# berthaBluetooth.net
KiCad netlist of a schematic drawn in EAGLE
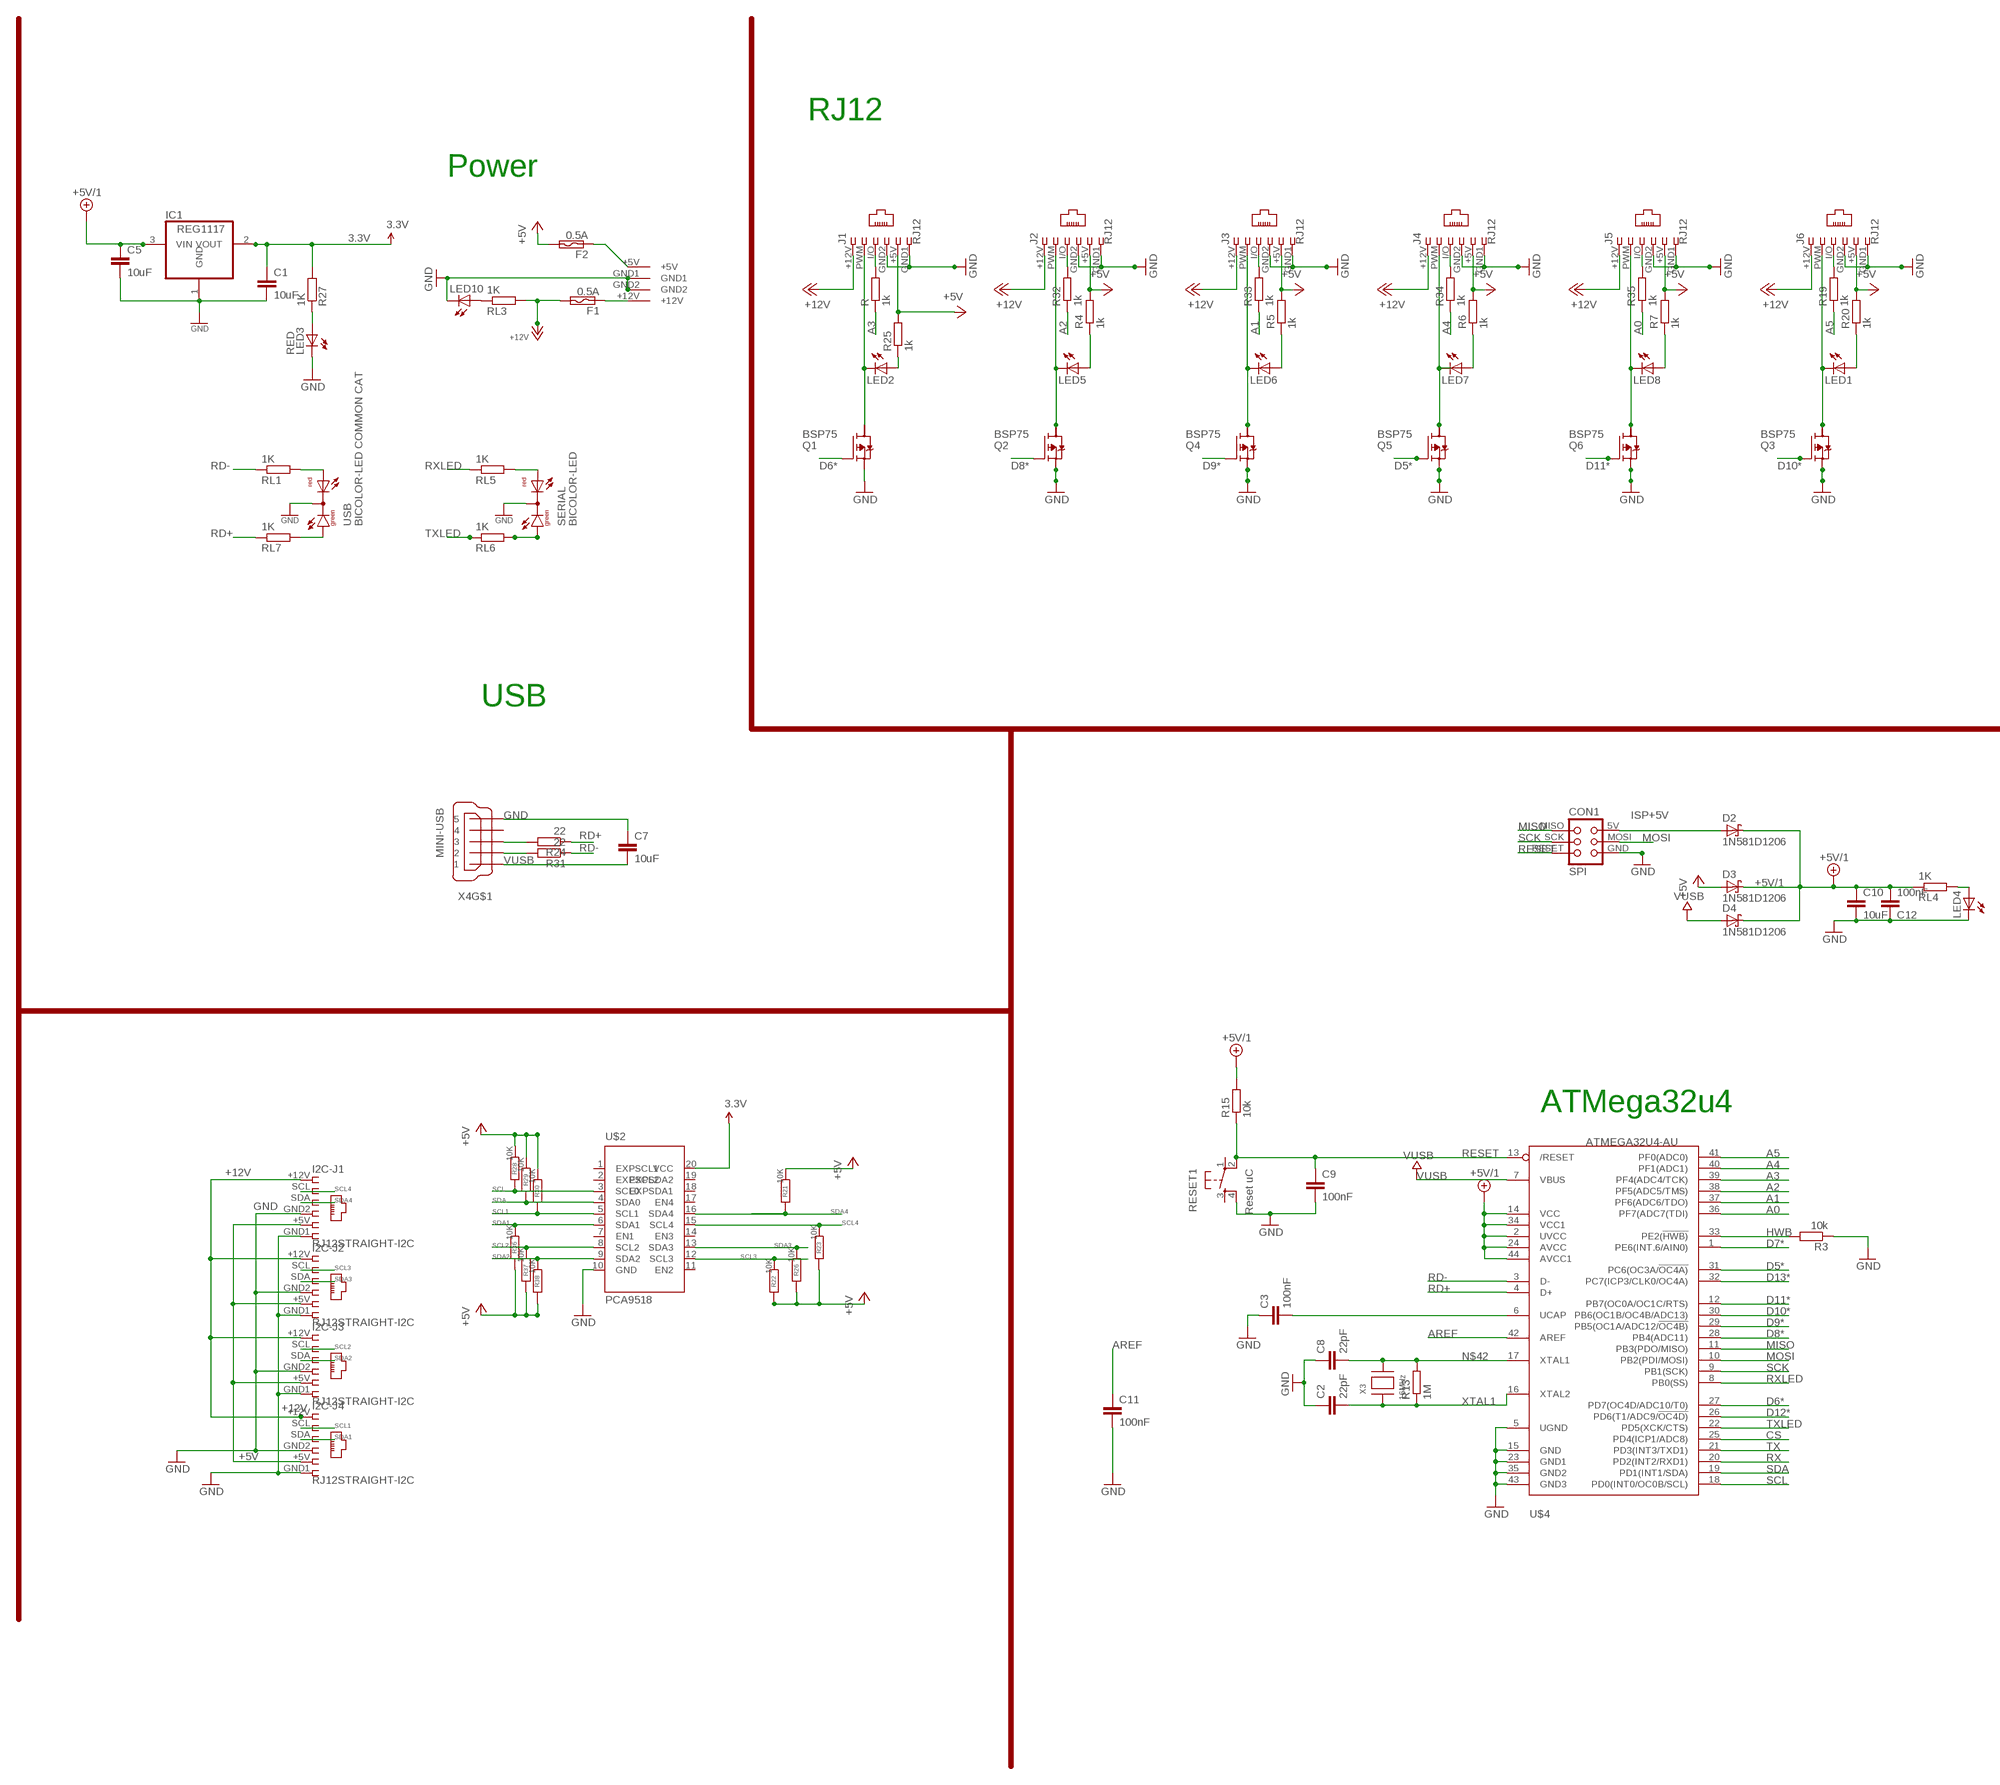
[diagram p0: schematic, sheet 1, part 1 of 2]
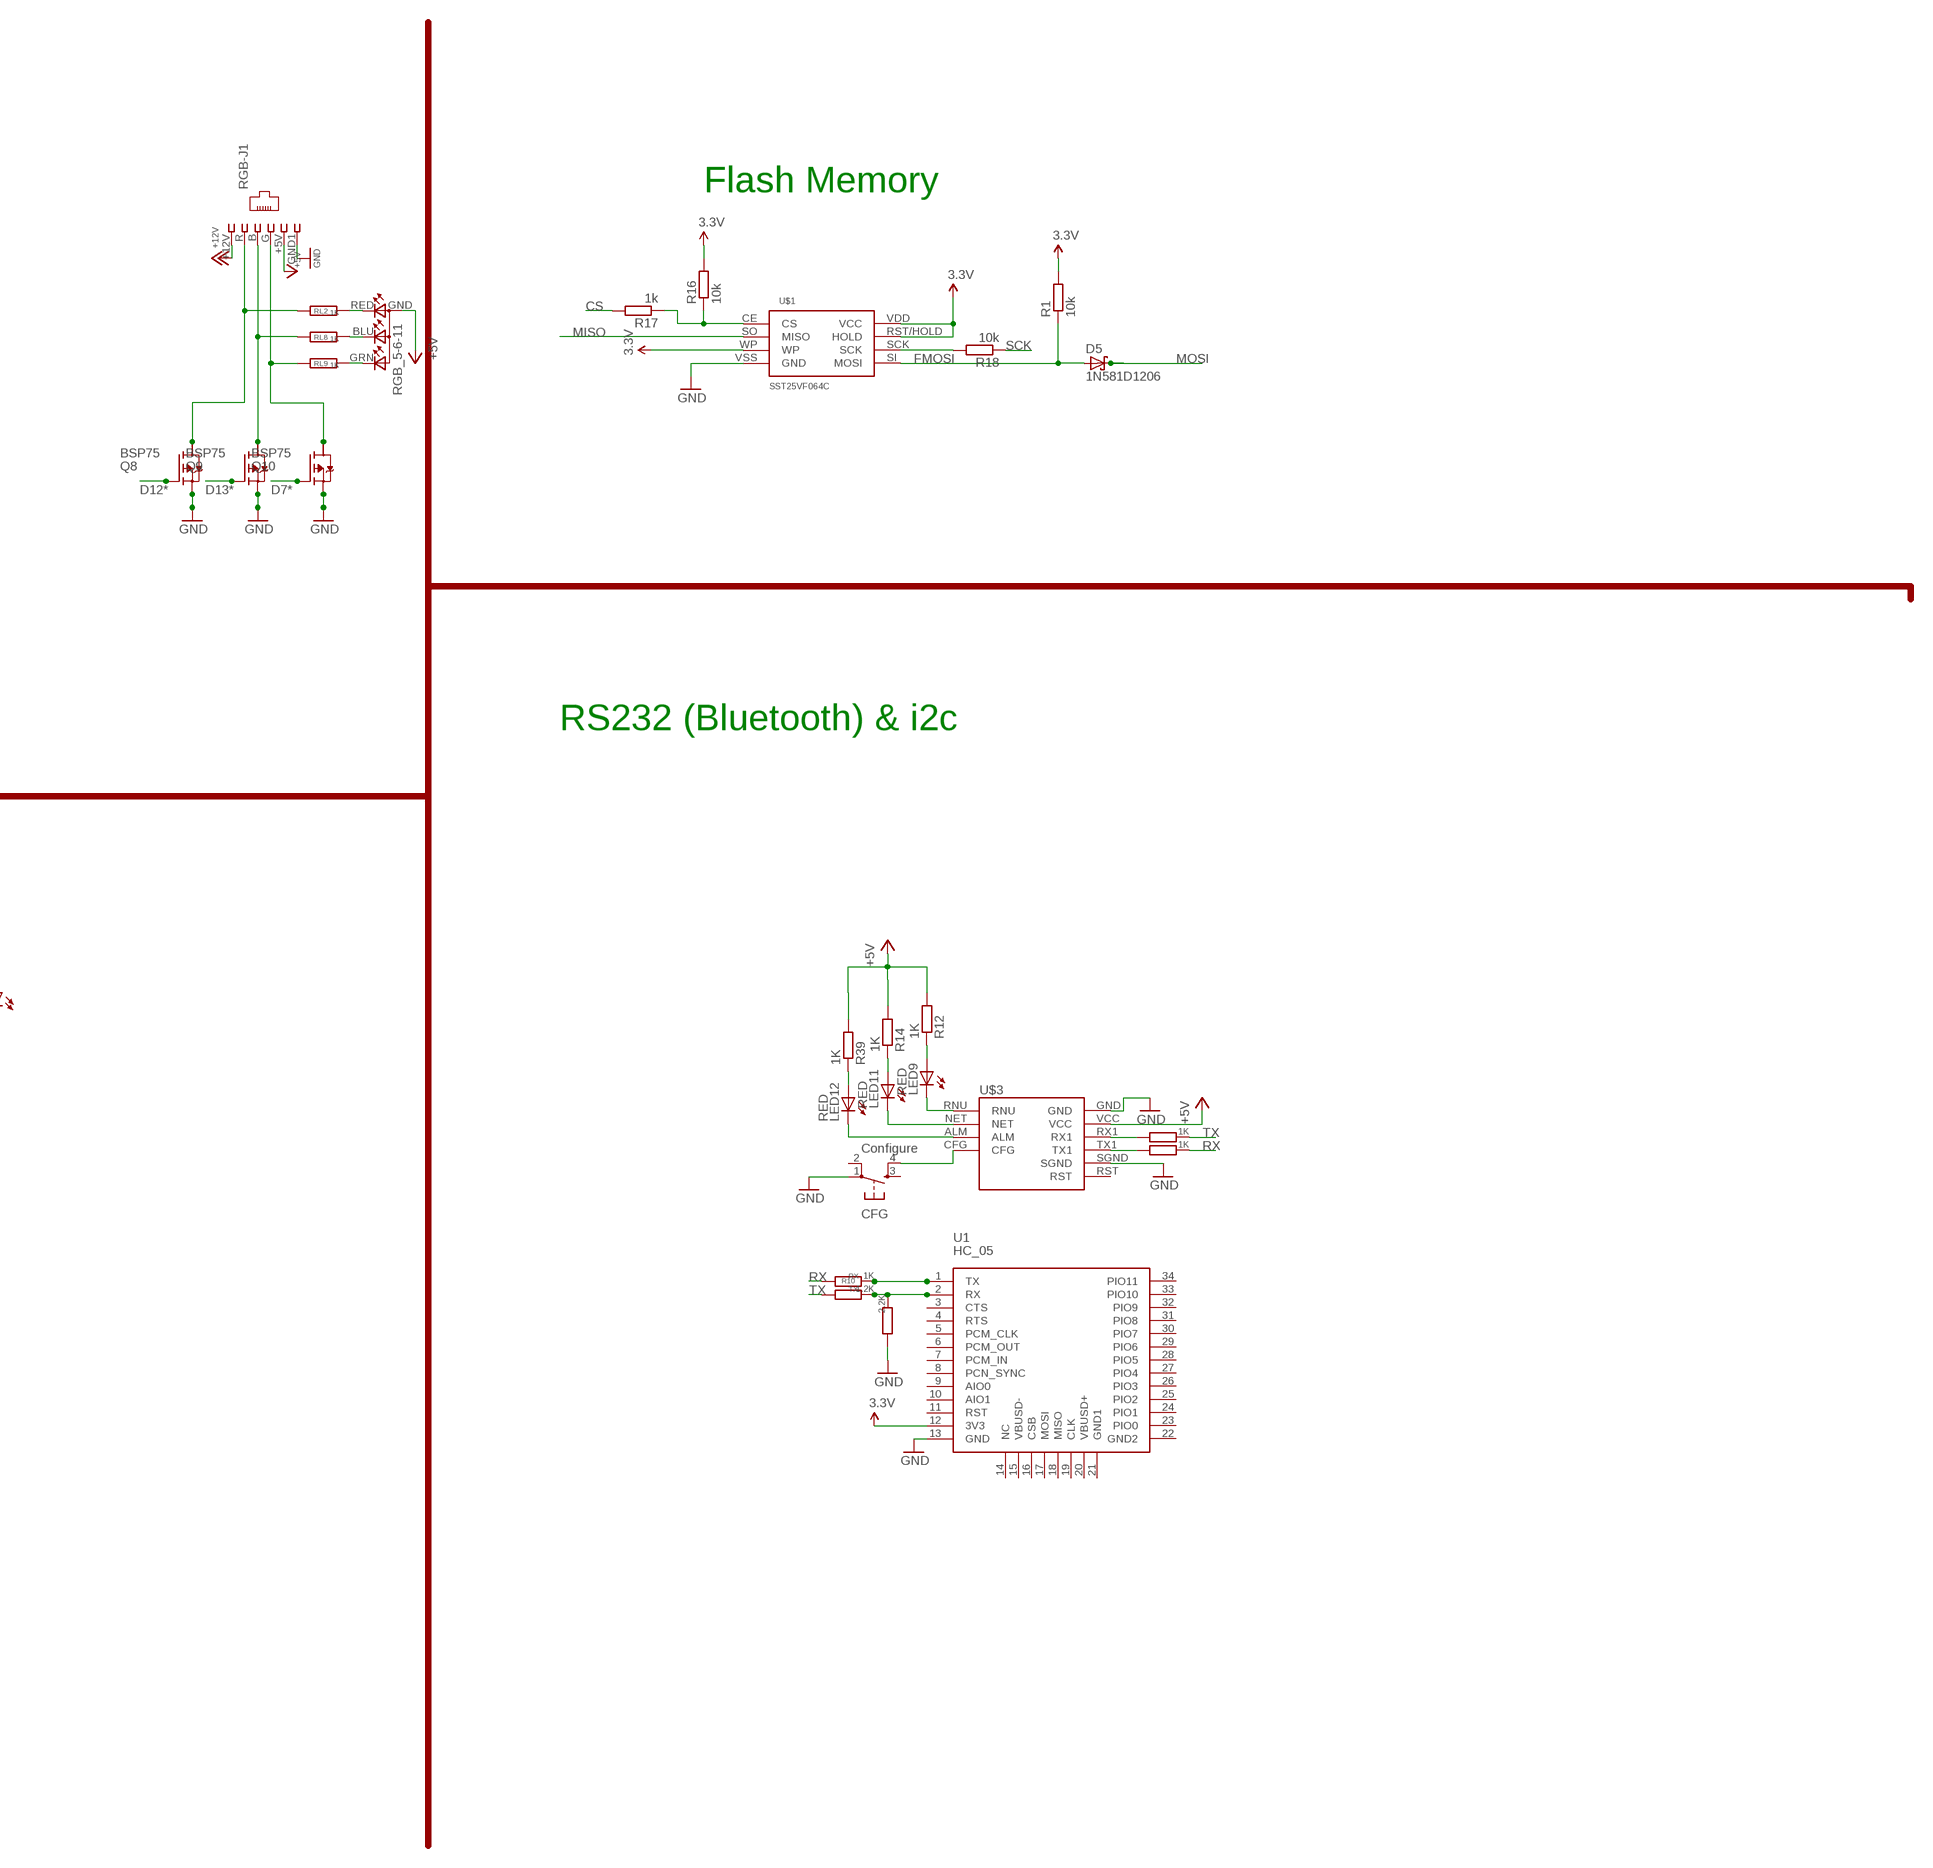
[diagram p1: schematic, sheet 1, part 2 of 2]

(export (version "E")
  (design (tool "Eeschema 10.0.6"))
  (components
    (comp (ref "C1")
      (value "10uF")
      (footprint "eagle-import:C1206")
      (libsource (lib "eagle-import") (part "C-EUC1206"))
    )
    (comp (ref "C2")
      (value "22pF")
      (footprint "eagle-import:C1206")
      (libsource (lib "eagle-import") (part "C-EUC1206"))
    )
    (comp (ref "C3")
      (value "100nF")
      (footprint "eagle-import:C1206")
      (libsource (lib "eagle-import") (part "C-EUC1206"))
    )
    (comp (ref "C5")
      (value "10uF")
      (footprint "eagle-import:C1206")
      (libsource (lib "eagle-import") (part "C-EUC1206"))
    )
    (comp (ref "C7")
      (value "10uF")
      (footprint "eagle-import:C1206")
      (libsource (lib "eagle-import") (part "C-EUC1206"))
    )
    (comp (ref "C8")
      (value "22pF")
      (footprint "eagle-import:C1206")
      (libsource (lib "eagle-import") (part "C-EUC1206"))
    )
    (comp (ref "C9")
      (value "100nF")
      (footprint "eagle-import:C1206")
      (libsource (lib "eagle-import") (part "C-EUC1206"))
    )
    (comp (ref "C10")
      (value "10uF")
      (footprint "eagle-import:C1206")
      (libsource (lib "eagle-import") (part "C-EUC1206"))
    )
    (comp (ref "C11")
      (value "100nF")
      (footprint "eagle-import:C1206")
      (libsource (lib "eagle-import") (part "C-EUC1206"))
    )
    (comp (ref "C12")
      (value "100nF")
      (footprint "eagle-import:C1206")
      (libsource (lib "eagle-import") (part "C-EUC1206"))
    )
    (comp (ref "CFG")
      (value "Configure")
      (footprint "eagle-import:TACTILE_SWITCH_SMD")
      (libsource (lib "eagle-import") (part "TAC_SWITCHSMD"))
    )
    (comp (ref "CON1")
      (value "SPI")
      (footprint "eagle-import:TC2030-MCP-NL")
      (libsource (lib "eagle-import") (part "TINYISPT"))
    )
    (comp (ref "D2")
      (value "1N581D1206")
      (footprint "eagle-import:LED-1206")
      (libsource (lib "eagle-import") (part "1N581D1206"))
    )
    (comp (ref "D3")
      (value "1N581D1206")
      (footprint "eagle-import:LED-1206")
      (libsource (lib "eagle-import") (part "1N581D1206"))
    )
    (comp (ref "D4")
      (value "1N581D1206")
      (footprint "eagle-import:LED-1206")
      (libsource (lib "eagle-import") (part "1N581D1206"))
    )
    (comp (ref "D5")
      (value "1N581D1206")
      (footprint "eagle-import:LED-1206")
      (libsource (lib "eagle-import") (part "1N581D1206"))
    )
    (comp (ref "F1")
      (value "0.5A")
      (footprint "eagle-import:C1812")
      (libsource (lib "eagle-import") (part "POLYSWITCHSMD1812"))
    )
    (comp (ref "F2")
      (value "0.5A")
      (footprint "eagle-import:C1812")
      (libsource (lib "eagle-import") (part "POLYSWITCHSMD1812"))
    )
    (comp (ref "I2C-J1")
      (value "RJ12STRAIGHT-I2C")
      (footprint "eagle-import:RJ12-STRAIGHT-I2C")
      (libsource (lib "eagle-import") (part "RJ12STRAIGHT-I2C"))
    )
    (comp (ref "I2C-J2")
      (value "RJ12STRAIGHT-I2C")
      (footprint "eagle-import:RJ12-STRAIGHT-I2C")
      (libsource (lib "eagle-import") (part "RJ12STRAIGHT-I2C"))
    )
    (comp (ref "I2C-J3")
      (value "RJ12STRAIGHT-I2C")
      (footprint "eagle-import:RJ12-STRAIGHT-I2C")
      (libsource (lib "eagle-import") (part "RJ12STRAIGHT-I2C"))
    )
    (comp (ref "I2C-J4")
      (value "RJ12STRAIGHT-I2C")
      (footprint "eagle-import:RJ12-STRAIGHT-I2C")
      (libsource (lib "eagle-import") (part "RJ12STRAIGHT-I2C"))
    )
    (comp (ref "IC1")
      (value "REG1117")
      (footprint "eagle-import:SOT223")
      (libsource (lib "eagle-import") (part "REG1117"))
    )
    (comp (ref "J1")
      (value "RJ12")
      (footprint "eagle-import:RJ12-STRAIGHT")
      (libsource (lib "eagle-import") (part "RJ12STRAIGHT"))
    )
    (comp (ref "J2")
      (value "RJ12")
      (footprint "eagle-import:RJ12-STRAIGHT")
      (libsource (lib "eagle-import") (part "RJ12STRAIGHT"))
    )
    (comp (ref "J3")
      (value "RJ12")
      (footprint "eagle-import:RJ12-STRAIGHT")
      (libsource (lib "eagle-import") (part "RJ12STRAIGHT"))
    )
    (comp (ref "J4")
      (value "RJ12")
      (footprint "eagle-import:RJ12-STRAIGHT")
      (libsource (lib "eagle-import") (part "RJ12STRAIGHT"))
    )
    (comp (ref "J5")
      (value "RJ12")
      (footprint "eagle-import:RJ12-STRAIGHT")
      (libsource (lib "eagle-import") (part "RJ12STRAIGHT"))
    )
    (comp (ref "J6")
      (value "RJ12")
      (footprint "eagle-import:RJ12-STRAIGHT")
      (libsource (lib "eagle-import") (part "RJ12STRAIGHT"))
    )
    (comp (ref "LED1")
      (value "Blue")
      (footprint "eagle-import:LED3MM")
      (libsource (lib "eagle-import") (part "lpatiny_LED3MM"))
    )
    (comp (ref "LED2")
      (value "Blue")
      (footprint "eagle-import:LED3MM")
      (libsource (lib "eagle-import") (part "lpatiny_LED3MM"))
    )
    (comp (ref "LED3")
      (value "RED")
      (footprint "eagle-import:CHIP-LED0805")
      (libsource (lib "eagle-import") (part "LEDCHIP-LED0805"))
    )
    (comp (ref "LED4")
      (value "RED")
      (footprint "eagle-import:LED3MM")
      (libsource (lib "eagle-import") (part "lpatiny_LED3MM"))
    )
    (comp (ref "LED5")
      (value "Blue")
      (footprint "eagle-import:LED3MM")
      (libsource (lib "eagle-import") (part "lpatiny_LED3MM"))
    )
    (comp (ref "LED6")
      (value "Blue")
      (footprint "eagle-import:LED3MM")
      (libsource (lib "eagle-import") (part "lpatiny_LED3MM"))
    )
    (comp (ref "LED7")
      (value "BLue")
      (footprint "eagle-import:LED3MM")
      (libsource (lib "eagle-import") (part "lpatiny_LED3MM"))
    )
    (comp (ref "LED8")
      (value "Blue")
      (footprint "eagle-import:LED3MM")
      (libsource (lib "eagle-import") (part "lpatiny_LED3MM"))
    )
    (comp (ref "LED9")
      (value "RED")
      (footprint "eagle-import:CHIP-LED0805")
      (libsource (lib "eagle-import") (part "LEDCHIP-LED0805"))
    )
    (comp (ref "LED10")
      (value "RED")
      (footprint "eagle-import:LED3MM")
      (libsource (lib "eagle-import") (part "lpatiny_LED3MM"))
    )
    (comp (ref "LED11")
      (value "RED")
      (footprint "eagle-import:CHIP-LED0805")
      (libsource (lib "eagle-import") (part "LEDCHIP-LED0805"))
    )
    (comp (ref "LED12")
      (value "RED")
      (footprint "eagle-import:CHIP-LED0805")
      (libsource (lib "eagle-import") (part "LEDCHIP-LED0805"))
    )
    (comp (ref "Q1")
      (value "BSP75")
      (footprint "eagle-import:PG-SOT-223")
      (libsource (lib "eagle-import") (part "BSP613P"))
    )
    (comp (ref "Q2")
      (value "BSP75")
      (footprint "eagle-import:PG-SOT-223")
      (libsource (lib "eagle-import") (part "BSP613P"))
    )
    (comp (ref "Q3")
      (value "BSP75")
      (footprint "eagle-import:PG-SOT-223")
      (libsource (lib "eagle-import") (part "BSP613P"))
    )
    (comp (ref "Q4")
      (value "BSP75")
      (footprint "eagle-import:PG-SOT-223")
      (libsource (lib "eagle-import") (part "BSP613P"))
    )
    (comp (ref "Q5")
      (value "BSP75")
      (footprint "eagle-import:PG-SOT-223")
      (libsource (lib "eagle-import") (part "BSP613P"))
    )
    (comp (ref "Q6")
      (value "BSP75")
      (footprint "eagle-import:PG-SOT-223")
      (libsource (lib "eagle-import") (part "BSP613P"))
    )
    (comp (ref "Q8")
      (value "BSP75")
      (footprint "eagle-import:PG-SOT-223")
      (libsource (lib "eagle-import") (part "BSP613P"))
    )
    (comp (ref "Q9")
      (value "BSP75")
      (footprint "eagle-import:PG-SOT-223")
      (libsource (lib "eagle-import") (part "BSP613P"))
    )
    (comp (ref "Q10")
      (value "BSP75")
      (footprint "eagle-import:PG-SOT-223")
      (libsource (lib "eagle-import") (part "BSP613P"))
    )
    (comp (ref "R")
      (value "1k")
      (footprint "eagle-import:R0805")
      (libsource (lib "eagle-import") (part "R-EU_R0805"))
    )
    (comp (ref "R1")
      (value "10k")
      (footprint "eagle-import:R0805")
      (libsource (lib "eagle-import") (part "R-EU_R0805"))
    )
    (comp (ref "R2")
      (value "2.2K")
      (footprint "eagle-import:R0805")
      (libsource (lib "eagle-import") (part "R-EU_R0805"))
    )
    (comp (ref "R3")
      (value "10k")
      (footprint "eagle-import:M0805")
      (libsource (lib "eagle-import") (part "resistor_R-EU_M0805"))
    )
    (comp (ref "R4")
      (value "1k")
      (footprint "eagle-import:R0805")
      (libsource (lib "eagle-import") (part "R-EU_R0805"))
    )
    (comp (ref "R5")
      (value "1k")
      (footprint "eagle-import:R0805")
      (libsource (lib "eagle-import") (part "R-EU_R0805"))
    )
    (comp (ref "R6")
      (value "1k")
      (footprint "eagle-import:R0805")
      (libsource (lib "eagle-import") (part "R-EU_R0805"))
    )
    (comp (ref "R7")
      (value "1k")
      (footprint "eagle-import:R0805")
      (libsource (lib "eagle-import") (part "R-EU_R0805"))
    )
    (comp (ref "R8")
      (value "1K")
      (footprint "eagle-import:R0805")
      (libsource (lib "eagle-import") (part "R-EU_R0805"))
    )
    (comp (ref "R9")
      (value "1.2K")
      (footprint "eagle-import:R0805")
      (libsource (lib "eagle-import") (part "R-EU_R0805"))
    )
    (comp (ref "R10")
      (value "1K")
      (footprint "eagle-import:R0805")
      (libsource (lib "eagle-import") (part "R-EU_R0805"))
    )
    (comp (ref "R11")
      (value "1K")
      (footprint "eagle-import:R0805")
      (libsource (lib "eagle-import") (part "R-EU_R0805"))
    )
    (comp (ref "R12")
      (value "1K")
      (footprint "eagle-import:R0805")
      (libsource (lib "eagle-import") (part "R-EU_R0805"))
    )
    (comp (ref "R13")
      (value "1M")
      (footprint "eagle-import:R1206")
      (libsource (lib "eagle-import") (part "R-EU_R1206"))
    )
    (comp (ref "R14")
      (value "1K")
      (footprint "eagle-import:R0805")
      (libsource (lib "eagle-import") (part "R-EU_R0805"))
    )
    (comp (ref "R15")
      (value "10k")
      (footprint "eagle-import:M0805")
      (libsource (lib "eagle-import") (part "resistor_R-EU_M0805"))
    )
    (comp (ref "R16")
      (value "10k")
      (footprint "eagle-import:R0805")
      (libsource (lib "eagle-import") (part "R-EU_R0805"))
    )
    (comp (ref "R17")
      (value "1k")
      (footprint "eagle-import:R0805")
      (libsource (lib "eagle-import") (part "R-EU_R0805"))
    )
    (comp (ref "R18")
      (value "10k")
      (footprint "eagle-import:R0805")
      (libsource (lib "eagle-import") (part "R-EU_R0805"))
    )
    (comp (ref "R19")
      (value "1k")
      (footprint "eagle-import:R0805")
      (libsource (lib "eagle-import") (part "R-EU_R0805"))
    )
    (comp (ref "R20")
      (value "1k")
      (footprint "eagle-import:R0805")
      (libsource (lib "eagle-import") (part "R-EU_R0805"))
    )
    (comp (ref "R21")
      (value "10K")
      (footprint "eagle-import:M0805")
      (libsource (lib "eagle-import") (part "resistor_R-EU_M0805"))
    )
    (comp (ref "R22")
      (value "10K")
      (footprint "eagle-import:M0805")
      (libsource (lib "eagle-import") (part "resistor_R-EU_M0805"))
    )
    (comp (ref "R23")
      (value "10K")
      (footprint "eagle-import:M0805")
      (libsource (lib "eagle-import") (part "resistor_R-EU_M0805"))
    )
    (comp (ref "R24")
      (value "22")
      (footprint "eagle-import:M1206")
      (libsource (lib "eagle-import") (part "resistor_R-EU_M1206"))
    )
    (comp (ref "R25")
      (value "1k")
      (footprint "eagle-import:R0805")
      (libsource (lib "eagle-import") (part "R-EU_R0805"))
    )
    (comp (ref "R26")
      (value "10K")
      (footprint "eagle-import:M0805")
      (libsource (lib "eagle-import") (part "resistor_R-EU_M0805"))
    )
    (comp (ref "R27")
      (value "1K")
      (footprint "eagle-import:R0805")
      (libsource (lib "eagle-import") (part "R-EU_R0805"))
    )
    (comp (ref "R28")
      (value "10K")
      (footprint "eagle-import:M0805")
      (libsource (lib "eagle-import") (part "resistor_R-EU_M0805"))
    )
    (comp (ref "R29")
      (value "10K")
      (footprint "eagle-import:M0805")
      (libsource (lib "eagle-import") (part "resistor_R-EU_M0805"))
    )
    (comp (ref "R30")
      (value "10K")
      (footprint "eagle-import:M0805")
      (libsource (lib "eagle-import") (part "resistor_R-EU_M0805"))
    )
    (comp (ref "R31")
      (value "22")
      (footprint "eagle-import:M1206")
      (libsource (lib "eagle-import") (part "resistor_R-EU_M1206"))
    )
    (comp (ref "R32")
      (value "1k")
      (footprint "eagle-import:R0805")
      (libsource (lib "eagle-import") (part "R-EU_R0805"))
    )
    (comp (ref "R33")
      (value "1k")
      (footprint "eagle-import:R0805")
      (libsource (lib "eagle-import") (part "R-EU_R0805"))
    )
    (comp (ref "R34")
      (value "1k")
      (footprint "eagle-import:R0805")
      (libsource (lib "eagle-import") (part "R-EU_R0805"))
    )
    (comp (ref "R35")
      (value "1k")
      (footprint "eagle-import:R0805")
      (libsource (lib "eagle-import") (part "R-EU_R0805"))
    )
    (comp (ref "R36")
      (value "10K")
      (footprint "eagle-import:M0805")
      (libsource (lib "eagle-import") (part "resistor_R-EU_M0805"))
    )
    (comp (ref "R37")
      (value "10K")
      (footprint "eagle-import:M0805")
      (libsource (lib "eagle-import") (part "resistor_R-EU_M0805"))
    )
    (comp (ref "R38")
      (value "10K")
      (footprint "eagle-import:M0805")
      (libsource (lib "eagle-import") (part "resistor_R-EU_M0805"))
    )
    (comp (ref "R39")
      (value "1K")
      (footprint "eagle-import:R0805")
      (libsource (lib "eagle-import") (part "R-EU_R0805"))
    )
    (comp (ref "RESET1")
      (value "Reset uC")
      (footprint "eagle-import:TACTILE_SWITCH_SMD")
      (libsource (lib "eagle-import") (part "TAC_SWITCHSMD"))
    )
    (comp (ref "RGB-J1")
      (value "RJ12")
      (footprint "eagle-import:RJ12-STRAIGHT-RGB")
      (libsource (lib "eagle-import") (part "RJ12STRAIGHT-RGB"))
    )
    (comp (ref "RGB_5-6-11")
      (value "TOPLED-3")
      (footprint "eagle-import:LED-TRICOLOR-THROUGHHOLE")
      (libsource (lib "eagle-import") (part "TOPLED-3"))
    )
    (comp (ref "RL1")
      (value "1K")
      (footprint "eagle-import:R0805")
      (libsource (lib "eagle-import") (part "R-EU_R0805"))
    )
    (comp (ref "RL2")
      (value "1K")
      (footprint "eagle-import:M0805")
      (libsource (lib "eagle-import") (part "resistor_R-EU_M0805"))
    )
    (comp (ref "RL3")
      (value "1K")
      (footprint "eagle-import:R0805")
      (libsource (lib "eagle-import") (part "R-EU_R0805"))
    )
    (comp (ref "RL4")
      (value "1K")
      (footprint "eagle-import:R0805")
      (libsource (lib "eagle-import") (part "resistor_R-EU_R0805"))
    )
    (comp (ref "RL5")
      (value "1K")
      (footprint "eagle-import:R0805")
      (libsource (lib "eagle-import") (part "R-EU_R0805"))
    )
    (comp (ref "RL6")
      (value "1K")
      (footprint "eagle-import:R0805")
      (libsource (lib "eagle-import") (part "R-EU_R0805"))
    )
    (comp (ref "RL7")
      (value "1K")
      (footprint "eagle-import:R0805")
      (libsource (lib "eagle-import") (part "R-EU_R0805"))
    )
    (comp (ref "RL8")
      (value "1K")
      (footprint "eagle-import:M0805")
      (libsource (lib "eagle-import") (part "resistor_R-EU_M0805"))
    )
    (comp (ref "RL9")
      (value "1K")
      (footprint "eagle-import:M0805")
      (libsource (lib "eagle-import") (part "resistor_R-EU_M0805"))
    )
    (comp (ref "SERIAL")
      (value "BICOLOR-LED")
      (footprint "eagle-import:BICOLOR-3MM")
      (libsource (lib "eagle-import") (part "BICOLOR-LED"))
    )
    (comp (ref "U$1")
      (value "SST25VF064C")
      (footprint "eagle-import:SOIC_8-LEAD")
      (libsource (lib "eagle-import") (part "SST25VF064C"))
    )
    (comp (ref "U$2")
      (value "PCA9518")
      (footprint "eagle-import:SO20W")
      (libsource (lib "eagle-import") (part "PCA9518"))
    )
    (comp (ref "U$3")
      (value "SZ05-ZIGBEE")
      (footprint "eagle-import:SZ05-ZIGBEE")
      (libsource (lib "eagle-import") (part "SZ05-ZIGBEE"))
    )
    (comp (ref "U$4")
      (value "ATMEGA32U4-AU")
      (footprint "eagle-import:TQFP44")
      (libsource (lib "eagle-import") (part "ATMEGA32U4-AU"))
    )
    (comp (ref "U$6")
      (value "KPJX-4S-S")
      (footprint "eagle-import:KPJX-4S-S")
      (libsource (lib "eagle-import") (part "KPJX-4S-S"))
    )
    (comp (ref "U1")
      (value "HC_05")
      (footprint "eagle-import:BLUETOOTH_SMD")
      (libsource (lib "eagle-import") (part "HC_05"))
    )
    (comp (ref "USB")
      (value "BICOLOR-LED COMMON CAT")
      (footprint "eagle-import:BICOLOR-3MM")
      (libsource (lib "eagle-import") (part "BICOLOR-LED"))
    )
    (comp (ref "X3")
      (value "16MHz")
      (footprint "eagle-import:NX6035")
      (libsource (lib "eagle-import") (part "XTALNX6035"))
    )
    (comp (ref "X4")
      (value "MINI-USB")
      (footprint "eagle-import:32005-201")
      (libsource (lib "eagle-import") (part "MINI-USB-SCHIELD-32005-201"))
    )
  )
  (nets
    (net (code "1") (name "+5V") (class "Default")
      (node (ref "D3") (pin "A") (pinfunction "A_A") (pintype "passive"))
      (node (ref "F2") (pin "2") (pinfunction "2_2") (pintype "passive"))
      (node (ref "I2C-J1") (pin "+5V") (pinfunction "5_+5V") (pintype "bidirectional"))
      (node (ref "I2C-J2") (pin "+5V") (pinfunction "5_+5V") (pintype "bidirectional"))
      (node (ref "I2C-J3") (pin "+5V") (pinfunction "5_+5V") (pintype "bidirectional"))
      (node (ref "I2C-J4") (pin "+5V") (pinfunction "5_+5V") (pintype "bidirectional"))
      (node (ref "J1") (pin "+5V") (pinfunction "5_+5V") (pintype "bidirectional"))
      (node (ref "J2") (pin "+5V") (pinfunction "5_+5V") (pintype "bidirectional"))
      (node (ref "J3") (pin "+5V") (pinfunction "5_+5V") (pintype "bidirectional"))
      (node (ref "J4") (pin "+5V") (pinfunction "5_+5V") (pintype "bidirectional"))
      (node (ref "J5") (pin "+5V") (pinfunction "5_+5V") (pintype "bidirectional"))
      (node (ref "J6") (pin "+5V") (pinfunction "5_+5V") (pintype "bidirectional"))
      (node (ref "R12") (pin "2") (pinfunction "2_2") (pintype "passive"))
      (node (ref "R14") (pin "2") (pinfunction "2_2") (pintype "passive"))
      (node (ref "R20") (pin "2") (pinfunction "2_2") (pintype "passive"))
      (node (ref "R21") (pin "1") (pinfunction "1_1") (pintype "passive"))
      (node (ref "R22") (pin "2") (pinfunction "2_2") (pintype "passive"))
      (node (ref "R23") (pin "2") (pinfunction "2_2") (pintype "passive"))
      (node (ref "R25") (pin "2") (pinfunction "2_2") (pintype "passive"))
      (node (ref "R26") (pin "2") (pinfunction "2_2") (pintype "passive"))
      (node (ref "R28") (pin "1") (pinfunction "1_1") (pintype "passive"))
      (node (ref "R29") (pin "1") (pinfunction "1_1") (pintype "passive"))
      (node (ref "R30") (pin "1") (pinfunction "1_1") (pintype "passive"))
      (node (ref "R36") (pin "2") (pinfunction "2_2") (pintype "passive"))
      (node (ref "R37") (pin "2") (pinfunction "2_2") (pintype "passive"))
      (node (ref "R38") (pin "2") (pinfunction "2_2") (pintype "passive"))
      (node (ref "R39") (pin "2") (pinfunction "2_2") (pintype "passive"))
      (node (ref "R4") (pin "2") (pinfunction "2_2") (pintype "passive"))
      (node (ref "R5") (pin "2") (pinfunction "2_2") (pintype "passive"))
      (node (ref "R6") (pin "2") (pinfunction "2_2") (pintype "passive"))
      (node (ref "R7") (pin "2") (pinfunction "2_2") (pintype "passive"))
      (node (ref "RGB-J1") (pin "+5V") (pinfunction "5_+5V") (pintype "bidirectional"))
      (node (ref "RGB_5-6-11") (pin "GND") (pinfunction "A2_GND") (pintype "passive"))
      (node (ref "U$3") (pin "VCC") (pinfunction "VCC_VCC") (pintype "bidirectional"))
    )
    (net (code "2") (name "+5V{slash}1") (class "Default")
      (node (ref "C10") (pin "1") (pinfunction "1_1") (pintype "passive"))
      (node (ref "C12") (pin "2") (pinfunction "2_2") (pintype "passive"))
      (node (ref "C5") (pin "1") (pinfunction "1_1") (pintype "passive"))
      (node (ref "D2") (pin "C") (pinfunction "C_C") (pintype "passive"))
      (node (ref "D3") (pin "C") (pinfunction "C_C") (pintype "passive"))
      (node (ref "D4") (pin "C") (pinfunction "C_C") (pintype "passive"))
      (node (ref "IC1") (pin "3") (pinfunction "VIN_3") (pintype "input"))
      (node (ref "R15") (pin "2") (pinfunction "2_2") (pintype "passive"))
      (node (ref "RL4") (pin "1") (pinfunction "1_1") (pintype "passive"))
      (node (ref "U$4") (pin "14") (pinfunction "VCC_14") (pintype "bidirectional"))
      (node (ref "U$4") (pin "2") (pinfunction "UVCC_2") (pintype "bidirectional"))
      (node (ref "U$4") (pin "24") (pinfunction "AVCC_24") (pintype "bidirectional"))
      (node (ref "U$4") (pin "34") (pinfunction "VCC1_34") (pintype "bidirectional"))
      (node (ref "U$4") (pin "44") (pinfunction "AVCC1_44") (pintype "bidirectional"))
    )
    (net (code "3") (name "+12V") (class "Default")
      (node (ref "F1") (pin "2") (pinfunction "2_2") (pintype "passive"))
      (node (ref "I2C-J1") (pin "+12V") (pinfunction "1_+12V") (pintype "bidirectional"))
      (node (ref "I2C-J2") (pin "+12V") (pinfunction "1_+12V") (pintype "bidirectional"))
      (node (ref "I2C-J3") (pin "+12V") (pinfunction "1_+12V") (pintype "bidirectional"))
      (node (ref "I2C-J4") (pin "+12V") (pinfunction "1_+12V") (pintype "bidirectional"))
      (node (ref "J1") (pin "+12V") (pinfunction "1_+12V") (pintype "bidirectional"))
      (node (ref "J2") (pin "+12V") (pinfunction "1_+12V") (pintype "bidirectional"))
      (node (ref "J3") (pin "+12V") (pinfunction "1_+12V") (pintype "bidirectional"))
      (node (ref "J4") (pin "+12V") (pinfunction "1_+12V") (pintype "bidirectional"))
      (node (ref "J5") (pin "+12V") (pinfunction "1_+12V") (pintype "bidirectional"))
      (node (ref "J6") (pin "+12V") (pinfunction "1_+12V") (pintype "bidirectional"))
      (node (ref "RGB-J1") (pin "+12V") (pinfunction "1_+12V") (pintype "bidirectional"))
      (node (ref "RL3") (pin "2") (pinfunction "2_2") (pintype "passive"))
    )
    (net (code "4") (name "/A0") (class "Default")
      (node (ref "R35") (pin "1") (pinfunction "1_1") (pintype "passive"))
      (node (ref "U$4") (pin "36") (pinfunction "PF7(ADC7(TDI)_36") (pintype "bidirectional"))
    )
    (net (code "5") (name "/A1") (class "Default")
      (node (ref "R33") (pin "1") (pinfunction "1_1") (pintype "passive"))
      (node (ref "U$4") (pin "37") (pinfunction "PF6(ADC6/TDO)_37") (pintype "bidirectional"))
    )
    (net (code "6") (name "/A2") (class "Default")
      (node (ref "R32") (pin "1") (pinfunction "1_1") (pintype "passive"))
      (node (ref "U$4") (pin "38") (pinfunction "PF5(ADC5/TMS)_38") (pintype "bidirectional"))
    )
    (net (code "7") (name "/A3") (class "Default")
      (node (ref "R") (pin "1") (pinfunction "1_1") (pintype "passive"))
      (node (ref "U$4") (pin "39") (pinfunction "PF4(ADC4/TCK)_39") (pintype "bidirectional"))
    )
    (net (code "8") (name "/A4") (class "Default")
      (node (ref "R34") (pin "1") (pinfunction "1_1") (pintype "passive"))
      (node (ref "U$4") (pin "40") (pinfunction "PF1(ADC1)_40") (pintype "bidirectional"))
    )
    (net (code "9") (name "/A5") (class "Default")
      (node (ref "R19") (pin "1") (pinfunction "1_1") (pintype "passive"))
      (node (ref "U$4") (pin "41") (pinfunction "PF0(ADC0)_41") (pintype "bidirectional"))
    )
    (net (code "10") (name "/AREF") (class "Default")
      (node (ref "C11") (pin "1") (pinfunction "1_1") (pintype "passive"))
      (node (ref "U$4") (pin "42") (pinfunction "AREF_42") (pintype "bidirectional"))
    )
    (net (code "11") (name "/CS") (class "Default")
      (node (ref "R17") (pin "2") (pinfunction "2_2") (pintype "passive"))
      (node (ref "U$4") (pin "25") (pinfunction "PD4(ICP1/ADC8)_25") (pintype "bidirectional"))
    )
    (net (code "12") (name "/D5*") (class "Default")
      (node (ref "Q5") (pin "1") (pinfunction "G_1") (pintype "passive"))
      (node (ref "U$4") (pin "31") (pinfunction "PC6(OC3A/~{OC4A})_31") (pintype "bidirectional"))
    )
    (net (code "13") (name "/D6*") (class "Default")
      (node (ref "Q1") (pin "1") (pinfunction "G_1") (pintype "passive"))
      (node (ref "U$4") (pin "27") (pinfunction "PD7(OC4D/ADC10/T0)_27") (pintype "bidirectional"))
    )
    (net (code "14") (name "/D7*") (class "Default")
      (node (ref "Q10") (pin "1") (pinfunction "G_1") (pintype "passive"))
      (node (ref "U$4") (pin "1") (pinfunction "PE6(INT.6/AIN0)_1") (pintype "bidirectional"))
    )
    (net (code "15") (name "/D8*") (class "Default")
      (node (ref "Q2") (pin "1") (pinfunction "G_1") (pintype "passive"))
      (node (ref "U$4") (pin "28") (pinfunction "PB4(ADC11)_28") (pintype "bidirectional"))
    )
    (net (code "16") (name "/D9*") (class "Default")
      (node (ref "Q4") (pin "1") (pinfunction "G_1") (pintype "passive"))
      (node (ref "U$4") (pin "29") (pinfunction "PB5(OC1A/ADC12/~{OC4B})_29") (pintype "bidirectional"))
    )
    (net (code "17") (name "/D10*") (class "Default")
      (node (ref "Q3") (pin "1") (pinfunction "G_1") (pintype "passive"))
      (node (ref "U$4") (pin "30") (pinfunction "PB6(OC1B/OC4B/ADC13)_30") (pintype "bidirectional"))
    )
    (net (code "18") (name "/D11*") (class "Default")
      (node (ref "Q6") (pin "1") (pinfunction "G_1") (pintype "passive"))
      (node (ref "U$4") (pin "12") (pinfunction "PB7(OC0A/OC1C/RTS)_12") (pintype "bidirectional"))
    )
    (net (code "19") (name "/D12*") (class "Default")
      (node (ref "Q8") (pin "1") (pinfunction "G_1") (pintype "passive"))
      (node (ref "U$4") (pin "26") (pinfunction "PD6(T1/ADC9/~{OC4D})_26") (pintype "bidirectional"))
    )
    (net (code "20") (name "/D13*") (class "Default")
      (node (ref "Q9") (pin "1") (pinfunction "G_1") (pintype "passive"))
      (node (ref "U$4") (pin "32") (pinfunction "PC7(ICP3/CLK0/OC4A)_32") (pintype "bidirectional"))
    )
    (net (code "21") (name "/FMOSI") (class "Default")
      (node (ref "D5") (pin "A") (pinfunction "A_A") (pintype "passive"))
      (node (ref "R1") (pin "1") (pinfunction "1_1") (pintype "passive"))
      (node (ref "U$1") (pin "SI") (pinfunction "MOSI_SI") (pintype "bidirectional"))
    )
    (net (code "22") (name "/HWB") (class "Default")
      (node (ref "R3") (pin "2") (pinfunction "2_2") (pintype "passive"))
      (node (ref "U$4") (pin "33") (pinfunction "PE2(~{HWB})_33") (pintype "bidirectional"))
    )
    (net (code "23") (name "/ISP+5V") (class "Default")
      (node (ref "CON1") (pin "5V") (pinfunction "VCC_5V") (pintype "passive"))
      (node (ref "D2") (pin "A") (pinfunction "A_A") (pintype "passive"))
    )
    (net (code "24") (name "/MISO") (class "Default")
      (node (ref "CON1") (pin "MISO") (pinfunction "MISO_MISO") (pintype "passive"))
      (node (ref "U$1") (pin "SO") (pinfunction "MISO_SO") (pintype "bidirectional"))
      (node (ref "U$4") (pin "11") (pinfunction "PB3(PDO/MISO)_11") (pintype "bidirectional"))
    )
    (net (code "25") (name "/MOSI") (class "Default")
      (node (ref "CON1") (pin "MOSI") (pinfunction "MOSI_MOSI") (pintype "passive"))
      (node (ref "D5") (pin "C") (pinfunction "C_C") (pintype "passive"))
      (node (ref "U$4") (pin "10") (pinfunction "PB2(PDI/MOSI)_10") (pintype "bidirectional"))
    )
    (net (code "26") (name "/N$42") (class "Default")
      (node (ref "C8") (pin "2") (pinfunction "2_2") (pintype "passive"))
      (node (ref "R13") (pin "2") (pinfunction "2_2") (pintype "passive"))
      (node (ref "U$4") (pin "17") (pinfunction "XTAL1_17") (pintype "bidirectional"))
      (node (ref "X3") (pin "P$2") (pinfunction "P$2_P$2") (pintype "bidirectional"))
    )
    (net (code "27") (name "/RD+") (class "Default")
      (node (ref "R24") (pin "1") (pinfunction "1_1") (pintype "passive"))
      (node (ref "RL7") (pin "1") (pinfunction "1_1") (pintype "passive"))
      (node (ref "U$4") (pin "4") (pinfunction "D+_4") (pintype "bidirectional"))
    )
    (net (code "28") (name "/RD-") (class "Default")
      (node (ref "R31") (pin "1") (pinfunction "1_1") (pintype "passive"))
      (node (ref "RL1") (pin "1") (pinfunction "1_1") (pintype "passive"))
      (node (ref "U$4") (pin "3") (pinfunction "D-_3") (pintype "bidirectional"))
    )
    (net (code "29") (name "/RESET") (class "Default")
      (node (ref "C9") (pin "1") (pinfunction "1_1") (pintype "passive"))
      (node (ref "CON1") (pin "RESET") (pinfunction "RESET_RESET") (pintype "passive"))
      (node (ref "R15") (pin "1") (pinfunction "1_1") (pintype "passive"))
      (node (ref "RESET1") (pin "2") (pinfunction "2_2") (pintype "passive"))
      (node (ref "U$4") (pin "13") (pinfunction "/RESET_13") (pintype "bidirectional"))
    )
    (net (code "30") (name "/RX") (class "Default")
      (node (ref "R10") (pin "2") (pinfunction "2_2") (pintype "passive"))
      (node (ref "R8") (pin "1") (pinfunction "1_1") (pintype "passive"))
      (node (ref "U$4") (pin "20") (pinfunction "PD2(INT2/RXD1)_20") (pintype "bidirectional"))
    )
    (net (code "31") (name "/RXLED") (class "Default")
      (node (ref "RL5") (pin "1") (pinfunction "1_1") (pintype "passive"))
      (node (ref "U$4") (pin "8") (pinfunction "PB0(SS)_8") (pintype "bidirectional"))
    )
    (net (code "32") (name "/SCK") (class "Default")
      (node (ref "CON1") (pin "SCK") (pinfunction "SCK_SCK") (pintype "passive"))
      (node (ref "R18") (pin "1") (pinfunction "1_1") (pintype "passive"))
      (node (ref "U$4") (pin "9") (pinfunction "PB1(SCK)_9") (pintype "bidirectional"))
    )
    (net (code "33") (name "/SCL") (class "Default")
      (node (ref "R28") (pin "2") (pinfunction "2_2") (pintype "passive"))
      (node (ref "U$2") (pin "3") (pinfunction "SCL0_3") (pintype "bidirectional"))
      (node (ref "U$4") (pin "18") (pinfunction "PD0(INT0/OC0B/SCL)_18") (pintype "bidirectional"))
    )
    (net (code "34") (name "/SCL1") (class "Default")
      (node (ref "I2C-J4") (pin "SCL") (pinfunction "2_SCL") (pintype "bidirectional"))
      (node (ref "R30") (pin "2") (pinfunction "2_2") (pintype "passive"))
      (node (ref "U$2") (pin "5") (pinfunction "SCL1_5") (pintype "bidirectional"))
    )
    (net (code "35") (name "/SCL2") (class "Default")
      (node (ref "I2C-J3") (pin "SCL") (pinfunction "2_SCL") (pintype "bidirectional"))
      (node (ref "R37") (pin "1") (pinfunction "1_1") (pintype "passive"))
      (node (ref "U$2") (pin "8") (pinfunction "SCL2_8") (pintype "bidirectional"))
    )
    (net (code "36") (name "/SCL3") (class "Default")
      (node (ref "I2C-J2") (pin "SCL") (pinfunction "2_SCL") (pintype "bidirectional"))
      (node (ref "R22") (pin "1") (pinfunction "1_1") (pintype "passive"))
      (node (ref "U$2") (pin "12") (pinfunction "SCL3_12") (pintype "bidirectional"))
    )
    (net (code "37") (name "/SCL4") (class "Default")
      (node (ref "I2C-J1") (pin "SCL") (pinfunction "2_SCL") (pintype "bidirectional"))
      (node (ref "R23") (pin "1") (pinfunction "1_1") (pintype "passive"))
      (node (ref "U$2") (pin "15") (pinfunction "SCL4_15") (pintype "bidirectional"))
    )
    (net (code "38") (name "/SDA") (class "Default")
      (node (ref "R29") (pin "2") (pinfunction "2_2") (pintype "passive"))
      (node (ref "U$2") (pin "4") (pinfunction "SDA0_4") (pintype "bidirectional"))
      (node (ref "U$4") (pin "19") (pinfunction "PD1(INT1/SDA)_19") (pintype "bidirectional"))
    )
    (net (code "39") (name "/SDA1") (class "Default")
      (node (ref "I2C-J4") (pin "SDA") (pinfunction "3_SDA") (pintype "bidirectional"))
      (node (ref "R36") (pin "1") (pinfunction "1_1") (pintype "passive"))
      (node (ref "U$2") (pin "6") (pinfunction "SDA1_6") (pintype "bidirectional"))
    )
    (net (code "40") (name "/SDA2") (class "Default")
      (node (ref "I2C-J3") (pin "SDA") (pinfunction "3_SDA") (pintype "bidirectional"))
      (node (ref "R38") (pin "1") (pinfunction "1_1") (pintype "passive"))
      (node (ref "U$2") (pin "9") (pinfunction "SDA2_9") (pintype "bidirectional"))
    )
    (net (code "41") (name "/SDA3") (class "Default")
      (node (ref "I2C-J2") (pin "SDA") (pinfunction "3_SDA") (pintype "bidirectional"))
      (node (ref "R26") (pin "1") (pinfunction "1_1") (pintype "passive"))
      (node (ref "U$2") (pin "13") (pinfunction "SDA3_13") (pintype "bidirectional"))
    )
    (net (code "42") (name "/SDA4") (class "Default")
      (node (ref "I2C-J1") (pin "SDA") (pinfunction "3_SDA") (pintype "bidirectional"))
      (node (ref "R21") (pin "2") (pinfunction "2_2") (pintype "passive"))
      (node (ref "U$2") (pin "16") (pinfunction "SDA4_16") (pintype "bidirectional"))
    )
    (net (code "43") (name "/TX") (class "Default")
      (node (ref "R11") (pin "1") (pinfunction "1_1") (pintype "passive"))
      (node (ref "R9") (pin "2") (pinfunction "2_2") (pintype "passive"))
      (node (ref "U$4") (pin "21") (pinfunction "PD3(INT3/TXD1)_21") (pintype "bidirectional"))
    )
    (net (code "44") (name "/TXLED") (class "Default")
      (node (ref "RL6") (pin "1") (pinfunction "1_1") (pintype "passive"))
      (node (ref "U$4") (pin "22") (pinfunction "PD5(XCK/CTS)_22") (pintype "bidirectional"))
    )
    (net (code "45") (name "/XTAL1") (class "Default")
      (node (ref "C2") (pin "2") (pinfunction "2_2") (pintype "passive"))
      (node (ref "R13") (pin "1") (pinfunction "1_1") (pintype "passive"))
      (node (ref "U$4") (pin "16") (pinfunction "XTAL2_16") (pintype "bidirectional"))
      (node (ref "X3") (pin "P$1") (pinfunction "P$1_P$1") (pintype "bidirectional"))
    )
    (net (code "46") (name "3.3V") (class "Default")
      (node (ref "C1") (pin "1") (pinfunction "1_1") (pintype "passive"))
      (node (ref "IC1") (pin "2") (pinfunction "VOUT_2") (pintype "output"))
      (node (ref "R1") (pin "2") (pinfunction "2_2") (pintype "passive"))
      (node (ref "R16") (pin "2") (pinfunction "2_2") (pintype "passive"))
      (node (ref "R27") (pin "2") (pinfunction "2_2") (pintype "passive"))
      (node (ref "U$1") (pin "RST/HOLD") (pinfunction "HOLD_RST/HOLD") (pintype "bidirectional"))
      (node (ref "U$1") (pin "VDD") (pinfunction "VCC_VDD") (pintype "bidirectional"))
      (node (ref "U$1") (pin "WP") (pinfunction "WP_WP") (pintype "bidirectional"))
      (node (ref "U$2") (pin "20") (pinfunction "VCC_20") (pintype "power_in"))
      (node (ref "U1") (pin "12") (pinfunction "3V3_12") (pintype "bidirectional"))
    )
    (net (code "47") (name "GND") (class "Default")
      (node (ref "C1") (pin "2") (pinfunction "2_2") (pintype "passive"))
      (node (ref "C10") (pin "2") (pinfunction "2_2") (pintype "passive"))
      (node (ref "C11") (pin "2") (pinfunction "2_2") (pintype "passive"))
      (node (ref "C12") (pin "1") (pinfunction "1_1") (pintype "passive"))
      (node (ref "C2") (pin "1") (pinfunction "1_1") (pintype "passive"))
      (node (ref "C3") (pin "1") (pinfunction "1_1") (pintype "passive"))
      (node (ref "C5") (pin "2") (pinfunction "2_2") (pintype "passive"))
      (node (ref "C7") (pin "1") (pinfunction "1_1") (pintype "passive"))
      (node (ref "C8") (pin "1") (pinfunction "1_1") (pintype "passive"))
      (node (ref "C9") (pin "2") (pinfunction "2_2") (pintype "passive"))
      (node (ref "CFG") (pin "1") (pinfunction "1_1") (pintype "passive"))
      (node (ref "CON1") (pin "GND") (pinfunction "GND_GND") (pintype "passive"))
      (node (ref "I2C-J1") (pin "GND1") (pinfunction "6_GND1") (pintype "bidirectional"))
      (node (ref "I2C-J1") (pin "GND2") (pinfunction "4_GND2") (pintype "bidirectional"))
      (node (ref "I2C-J2") (pin "GND1") (pinfunction "6_GND1") (pintype "bidirectional"))
      (node (ref "I2C-J2") (pin "GND2") (pinfunction "4_GND2") (pintype "bidirectional"))
      (node (ref "I2C-J3") (pin "GND1") (pinfunction "6_GND1") (pintype "bidirectional"))
      (node (ref "I2C-J3") (pin "GND2") (pinfunction "4_GND2") (pintype "bidirectional"))
      (node (ref "I2C-J4") (pin "GND1") (pinfunction "6_GND1") (pintype "bidirectional"))
      (node (ref "I2C-J4") (pin "GND2") (pinfunction "4_GND2") (pintype "bidirectional"))
      (node (ref "IC1") (pin "1") (pinfunction "GND_1") (pintype "power_in"))
      (node (ref "J1") (pin "GND1") (pinfunction "6_GND1") (pintype "bidirectional"))
      (node (ref "J1") (pin "GND2") (pinfunction "4_GND2") (pintype "bidirectional"))
      (node (ref "J2") (pin "GND1") (pinfunction "6_GND1") (pintype "bidirectional"))
      (node (ref "J2") (pin "GND2") (pinfunction "4_GND2") (pintype "bidirectional"))
      (node (ref "J3") (pin "GND1") (pinfunction "6_GND1") (pintype "bidirectional"))
      (node (ref "J3") (pin "GND2") (pinfunction "4_GND2") (pintype "bidirectional"))
      (node (ref "J4") (pin "GND1") (pinfunction "6_GND1") (pintype "bidirectional"))
      (node (ref "J4") (pin "GND2") (pinfunction "4_GND2") (pintype "bidirectional"))
      (node (ref "J5") (pin "GND1") (pinfunction "6_GND1") (pintype "bidirectional"))
      (node (ref "J5") (pin "GND2") (pinfunction "4_GND2") (pintype "bidirectional"))
      (node (ref "J6") (pin "GND1") (pinfunction "6_GND1") (pintype "bidirectional"))
      (node (ref "J6") (pin "GND2") (pinfunction "4_GND2") (pintype "bidirectional"))
      (node (ref "LED10") (pin "K") (pinfunction "C_K") (pintype "passive"))
      (node (ref "LED3") (pin "C") (pinfunction "C_C") (pintype "passive"))
      (node (ref "LED4") (pin "K") (pinfunction "C_K") (pintype "passive"))
      (node (ref "Q1") (pin "3") (pinfunction "S_3") (pintype "passive"))
      (node (ref "Q10") (pin "3") (pinfunction "S_3") (pintype "passive"))
      (node (ref "Q2") (pin "3") (pinfunction "S_3") (pintype "passive"))
      (node (ref "Q3") (pin "3") (pinfunction "S_3") (pintype "passive"))
      (node (ref "Q4") (pin "3") (pinfunction "S_3") (pintype "passive"))
      (node (ref "Q5") (pin "3") (pinfunction "S_3") (pintype "passive"))
      (node (ref "Q6") (pin "3") (pinfunction "S_3") (pintype "passive"))
      (node (ref "Q8") (pin "3") (pinfunction "S_3") (pintype "passive"))
      (node (ref "Q9") (pin "3") (pinfunction "S_3") (pintype "passive"))
      (node (ref "R2") (pin "2") (pinfunction "2_2") (pintype "passive"))
      (node (ref "R3") (pin "1") (pinfunction "1_1") (pintype "passive"))
      (node (ref "RESET1") (pin "4") (pinfunction "4_4") (pintype "passive"))
      (node (ref "RGB-J1") (pin "GND1") (pinfunction "6_GND1") (pintype "bidirectional"))
      (node (ref "SERIAL") (pin "2") (pinfunction "C_2") (pintype "passive"))
      (node (ref "U$1") (pin "VSS") (pinfunction "GND_VSS") (pintype "bidirectional"))
      (node (ref "U$2") (pin "10") (pinfunction "GND_10") (pintype "power_in"))
      (node (ref "U$3") (pin "GND") (pinfunction "GND_GND") (pintype "bidirectional"))
      (node (ref "U$3") (pin "SGND") (pinfunction "SGND_SGND") (pintype "bidirectional"))
      (node (ref "U$4") (pin "15") (pinfunction "GND_15") (pintype "bidirectional"))
      (node (ref "U$4") (pin "23") (pinfunction "GND1_23") (pintype "bidirectional"))
      (node (ref "U$4") (pin "35") (pinfunction "GND2_35") (pintype "bidirectional"))
      (node (ref "U$4") (pin "43") (pinfunction "GND3_43") (pintype "bidirectional"))
      (node (ref "U$4") (pin "5") (pinfunction "UGND_5") (pintype "bidirectional"))
      (node (ref "U$6") (pin "GND1") (pinfunction "GND1_GND1") (pintype "input"))
      (node (ref "U$6") (pin "GND2") (pinfunction "GND2_GND2") (pintype "input"))
      (node (ref "U1") (pin "13") (pinfunction "GND_13") (pintype "bidirectional"))
      (node (ref "USB") (pin "2") (pinfunction "C_2") (pintype "passive"))
      (node (ref "X4") (pin "5") (pinfunction "5_5") (pintype "passive"))
    )
    (net (code "48") (name "Net-(CFG-Pad4)") (class "Default")
      (node (ref "CFG") (pin "4") (pinfunction "4_4") (pintype "passive"))
      (node (ref "U$3") (pin "CFG") (pinfunction "CFG_CFG") (pintype "bidirectional"))
    )
    (net (code "49") (name "Net-(F1-Pad1)") (class "Default")
      (node (ref "F1") (pin "1") (pinfunction "1_1") (pintype "passive"))
      (node (ref "U$6") (pin "+12V") (pinfunction "+12V_+12V") (pintype "power_in"))
    )
    (net (code "50") (name "Net-(F2-Pad1)") (class "Default")
      (node (ref "F2") (pin "1") (pinfunction "1_1") (pintype "passive"))
      (node (ref "U$6") (pin "+5V") (pinfunction "+5V_+5V") (pintype "power_in"))
    )
    (net (code "51") (name "Net-(J1-2)") (class "Default")
      (node (ref "J1") (pin "PWM") (pinfunction "2_PWM") (pintype "bidirectional"))
      (node (ref "LED2") (pin "K") (pinfunction "C_K") (pintype "passive"))
      (node (ref "Q1") (pin "2") (pinfunction "D_2") (pintype "passive"))
    )
    (net (code "52") (name "Net-(J1-3)") (class "Default")
      (node (ref "J1") (pin "I/O") (pinfunction "3_I/O") (pintype "bidirectional"))
      (node (ref "R") (pin "2") (pinfunction "2_2") (pintype "passive"))
    )
    (net (code "53") (name "Net-(J2-2)") (class "Default")
      (node (ref "J2") (pin "PWM") (pinfunction "2_PWM") (pintype "bidirectional"))
      (node (ref "LED5") (pin "K") (pinfunction "C_K") (pintype "passive"))
      (node (ref "Q2") (pin "2") (pinfunction "D_2") (pintype "passive"))
    )
    (net (code "54") (name "Net-(J2-3)") (class "Default")
      (node (ref "J2") (pin "I/O") (pinfunction "3_I/O") (pintype "bidirectional"))
      (node (ref "R32") (pin "2") (pinfunction "2_2") (pintype "passive"))
    )
    (net (code "55") (name "Net-(J3-2)") (class "Default")
      (node (ref "J3") (pin "PWM") (pinfunction "2_PWM") (pintype "bidirectional"))
      (node (ref "LED6") (pin "K") (pinfunction "C_K") (pintype "passive"))
      (node (ref "Q4") (pin "2") (pinfunction "D_2") (pintype "passive"))
    )
    (net (code "56") (name "Net-(J3-3)") (class "Default")
      (node (ref "J3") (pin "I/O") (pinfunction "3_I/O") (pintype "bidirectional"))
      (node (ref "R33") (pin "2") (pinfunction "2_2") (pintype "passive"))
    )
    (net (code "57") (name "Net-(J4-2)") (class "Default")
      (node (ref "J4") (pin "PWM") (pinfunction "2_PWM") (pintype "bidirectional"))
      (node (ref "LED7") (pin "K") (pinfunction "C_K") (pintype "passive"))
      (node (ref "Q5") (pin "2") (pinfunction "D_2") (pintype "passive"))
    )
    (net (code "58") (name "Net-(J4-3)") (class "Default")
      (node (ref "J4") (pin "I/O") (pinfunction "3_I/O") (pintype "bidirectional"))
      (node (ref "R34") (pin "2") (pinfunction "2_2") (pintype "passive"))
    )
    (net (code "59") (name "Net-(J5-2)") (class "Default")
      (node (ref "J5") (pin "PWM") (pinfunction "2_PWM") (pintype "bidirectional"))
      (node (ref "LED8") (pin "K") (pinfunction "C_K") (pintype "passive"))
      (node (ref "Q6") (pin "2") (pinfunction "D_2") (pintype "passive"))
    )
    (net (code "60") (name "Net-(J5-3)") (class "Default")
      (node (ref "J5") (pin "I/O") (pinfunction "3_I/O") (pintype "bidirectional"))
      (node (ref "R35") (pin "2") (pinfunction "2_2") (pintype "passive"))
    )
    (net (code "61") (name "Net-(J6-2)") (class "Default")
      (node (ref "J6") (pin "PWM") (pinfunction "2_PWM") (pintype "bidirectional"))
      (node (ref "LED1") (pin "K") (pinfunction "C_K") (pintype "passive"))
      (node (ref "Q3") (pin "2") (pinfunction "D_2") (pintype "passive"))
    )
    (net (code "62") (name "Net-(J6-3)") (class "Default")
      (node (ref "J6") (pin "I/O") (pinfunction "3_I/O") (pintype "bidirectional"))
      (node (ref "R19") (pin "2") (pinfunction "2_2") (pintype "passive"))
    )
    (net (code "63") (name "Net-(LED1-PadA)") (class "Default")
      (node (ref "LED1") (pin "A") (pinfunction "A_A") (pintype "passive"))
      (node (ref "R20") (pin "1") (pinfunction "1_1") (pintype "passive"))
    )
    (net (code "64") (name "Net-(LED2-PadA)") (class "Default")
      (node (ref "LED2") (pin "A") (pinfunction "A_A") (pintype "passive"))
      (node (ref "R25") (pin "1") (pinfunction "1_1") (pintype "passive"))
    )
    (net (code "65") (name "Net-(LED3-PadA)") (class "Default")
      (node (ref "LED3") (pin "A") (pinfunction "A_A") (pintype "passive"))
      (node (ref "R27") (pin "1") (pinfunction "1_1") (pintype "passive"))
    )
    (net (code "66") (name "Net-(LED4-PadA)") (class "Default")
      (node (ref "LED4") (pin "A") (pinfunction "A_A") (pintype "passive"))
      (node (ref "RL4") (pin "2") (pinfunction "2_2") (pintype "passive"))
    )
    (net (code "67") (name "Net-(LED5-PadA)") (class "Default")
      (node (ref "LED5") (pin "A") (pinfunction "A_A") (pintype "passive"))
      (node (ref "R4") (pin "1") (pinfunction "1_1") (pintype "passive"))
    )
    (net (code "68") (name "Net-(LED6-PadA)") (class "Default")
      (node (ref "LED6") (pin "A") (pinfunction "A_A") (pintype "passive"))
      (node (ref "R5") (pin "1") (pinfunction "1_1") (pintype "passive"))
    )
    (net (code "69") (name "Net-(LED7-PadA)") (class "Default")
      (node (ref "LED7") (pin "A") (pinfunction "A_A") (pintype "passive"))
      (node (ref "R6") (pin "1") (pinfunction "1_1") (pintype "passive"))
    )
    (net (code "70") (name "Net-(LED8-PadA)") (class "Default")
      (node (ref "LED8") (pin "A") (pinfunction "A_A") (pintype "passive"))
      (node (ref "R7") (pin "1") (pinfunction "1_1") (pintype "passive"))
    )
    (net (code "71") (name "Net-(LED9-PadA)") (class "Default")
      (node (ref "LED9") (pin "A") (pinfunction "A_A") (pintype "passive"))
      (node (ref "R12") (pin "1") (pinfunction "1_1") (pintype "passive"))
    )
    (net (code "72") (name "Net-(LED9-PadC)") (class "Default")
      (node (ref "LED9") (pin "C") (pinfunction "C_C") (pintype "passive"))
      (node (ref "U$3") (pin "RNU") (pinfunction "RNU_RNU") (pintype "bidirectional"))
    )
    (net (code "73") (name "Net-(LED10-PadA)") (class "Default")
      (node (ref "LED10") (pin "A") (pinfunction "A_A") (pintype "passive"))
      (node (ref "RL3") (pin "1") (pinfunction "1_1") (pintype "passive"))
    )
    (net (code "74") (name "Net-(LED11-PadA)") (class "Default")
      (node (ref "LED11") (pin "A") (pinfunction "A_A") (pintype "passive"))
      (node (ref "R14") (pin "1") (pinfunction "1_1") (pintype "passive"))
    )
    (net (code "75") (name "Net-(LED11-PadC)") (class "Default")
      (node (ref "LED11") (pin "C") (pinfunction "C_C") (pintype "passive"))
      (node (ref "U$3") (pin "NET") (pinfunction "NET_NET") (pintype "bidirectional"))
    )
    (net (code "76") (name "Net-(LED12-PadA)") (class "Default")
      (node (ref "LED12") (pin "A") (pinfunction "A_A") (pintype "passive"))
      (node (ref "R39") (pin "1") (pinfunction "1_1") (pintype "passive"))
    )
    (net (code "77") (name "Net-(LED12-PadC)") (class "Default")
      (node (ref "LED12") (pin "C") (pinfunction "C_C") (pintype "passive"))
      (node (ref "U$3") (pin "ALM") (pinfunction "ALM_ALM") (pintype "bidirectional"))
    )
    (net (code "78") (name "Net-(R8-Pad2)") (class "Default")
      (node (ref "R8") (pin "2") (pinfunction "2_2") (pintype "passive"))
      (node (ref "U$3") (pin "TX1") (pinfunction "TX1_TX1") (pintype "bidirectional"))
    )
    (net (code "79") (name "Net-(R11-Pad2)") (class "Default")
      (node (ref "R11") (pin "2") (pinfunction "2_2") (pintype "passive"))
      (node (ref "U$3") (pin "RX1") (pinfunction "RX1_RX1") (pintype "bidirectional"))
    )
    (net (code "80") (name "Net-(R18-Pad2)") (class "Default")
      (node (ref "R18") (pin "2") (pinfunction "2_2") (pintype "passive"))
      (node (ref "U$1") (pin "SCK") (pinfunction "SCK_SCK") (pintype "bidirectional"))
    )
    (net (code "81") (name "Net-(R24-Pad2)") (class "Default")
      (node (ref "R24") (pin "2") (pinfunction "2_2") (pintype "passive"))
      (node (ref "X4") (pin "3") (pinfunction "3_3") (pintype "passive"))
    )
    (net (code "82") (name "Net-(R31-Pad2)") (class "Default")
      (node (ref "R31") (pin "2") (pinfunction "2_2") (pintype "passive"))
      (node (ref "X4") (pin "2") (pinfunction "2_2") (pintype "passive"))
    )
    (net (code "83") (name "Net-(RGB-J1-2)") (class "Default")
      (node (ref "Q8") (pin "2") (pinfunction "D_2") (pintype "passive"))
      (node (ref "RGB-J1") (pin "R") (pinfunction "2_R") (pintype "bidirectional"))
      (node (ref "RL2") (pin "1") (pinfunction "1_1") (pintype "passive"))
    )
    (net (code "84") (name "Net-(RGB-J1-3)") (class "Default")
      (node (ref "Q9") (pin "2") (pinfunction "D_2") (pintype "passive"))
      (node (ref "RGB-J1") (pin "B") (pinfunction "3_B") (pintype "bidirectional"))
      (node (ref "RL8") (pin "1") (pinfunction "1_1") (pintype "passive"))
    )
    (net (code "85") (name "Net-(RGB-J1-4)") (class "Default")
      (node (ref "Q10") (pin "2") (pinfunction "D_2") (pintype "passive"))
      (node (ref "RGB-J1") (pin "G") (pinfunction "4_G") (pintype "bidirectional"))
      (node (ref "RL9") (pin "1") (pinfunction "1_1") (pintype "passive"))
    )
    (net (code "86") (name "Net-(RGB_5-6-11-CBLUE)") (class "Default")
      (node (ref "RGB_5-6-11") (pin "BLU") (pinfunction "CBLUE_BLU") (pintype "passive"))
      (node (ref "RL8") (pin "2") (pinfunction "2_2") (pintype "passive"))
    )
    (net (code "87") (name "Net-(RGB_5-6-11-CGREEN)") (class "Default")
      (node (ref "RGB_5-6-11") (pin "GRN") (pinfunction "CGREEN_GRN") (pintype "passive"))
      (node (ref "RL9") (pin "2") (pinfunction "2_2") (pintype "passive"))
    )
    (net (code "88") (name "Net-(RGB_5-6-11-CRED)") (class "Default")
      (node (ref "RGB_5-6-11") (pin "RED") (pinfunction "CRED_RED") (pintype "passive"))
      (node (ref "RL2") (pin "2") (pinfunction "2_2") (pintype "passive"))
    )
    (net (code "89") (name "Net-(SERIAL-AG)") (class "Default")
      (node (ref "RL6") (pin "2") (pinfunction "2_2") (pintype "passive"))
      (node (ref "SERIAL") (pin "1") (pinfunction "AG_1") (pintype "passive"))
    )
    (net (code "90") (name "Net-(SERIAL-AR)") (class "Default")
      (node (ref "RL5") (pin "2") (pinfunction "2_2") (pintype "passive"))
      (node (ref "SERIAL") (pin "3") (pinfunction "AR_3") (pintype "passive"))
    )
    (net (code "91") (name "Net-(U$1-CS)") (class "Default")
      (node (ref "R16") (pin "1") (pinfunction "1_1") (pintype "passive"))
      (node (ref "R17") (pin "1") (pinfunction "1_1") (pintype "passive"))
      (node (ref "U$1") (pin "CE") (pinfunction "CS_CE") (pintype "bidirectional"))
    )
    (net (code "92") (name "Net-(U$4-UCAP)") (class "Default")
      (node (ref "C3") (pin "2") (pinfunction "2_2") (pintype "passive"))
      (node (ref "U$4") (pin "6") (pinfunction "UCAP_6") (pintype "bidirectional"))
    )
    (net (code "93") (name "Net-(U1-RX)") (class "Default")
      (node (ref "R2") (pin "1") (pinfunction "1_1") (pintype "passive"))
      (node (ref "R9") (pin "1") (pinfunction "1_1") (pintype "passive"))
      (node (ref "U1") (pin "2") (pinfunction "RX_2") (pintype "bidirectional"))
    )
    (net (code "94") (name "Net-(U1-TX)") (class "Default")
      (node (ref "R10") (pin "1") (pinfunction "1_1") (pintype "passive"))
      (node (ref "U1") (pin "1") (pinfunction "TX_1") (pintype "bidirectional"))
    )
    (net (code "95") (name "Net-(USB-AG)") (class "Default")
      (node (ref "RL7") (pin "2") (pinfunction "2_2") (pintype "passive"))
      (node (ref "USB") (pin "1") (pinfunction "AG_1") (pintype "passive"))
    )
    (net (code "96") (name "Net-(USB-AR)") (class "Default")
      (node (ref "RL1") (pin "2") (pinfunction "2_2") (pintype "passive"))
      (node (ref "USB") (pin "3") (pinfunction "AR_3") (pintype "passive"))
    )
    (net (code "97") (name "VUSB") (class "Default")
      (node (ref "C7") (pin "2") (pinfunction "2_2") (pintype "passive"))
      (node (ref "D4") (pin "A") (pinfunction "A_A") (pintype "passive"))
      (node (ref "U$4") (pin "7") (pinfunction "VBUS_7") (pintype "bidirectional"))
      (node (ref "X4") (pin "1") (pinfunction "1_1") (pintype "passive"))
    )
    (net (code "98") (name "unconnected-(CFG-Pad2)") (class "Default")
      (node (ref "CFG") (pin "2") (pinfunction "2_2") (pintype "passive"))
    )
    (net (code "99") (name "unconnected-(CFG-Pad3)") (class "Default")
      (node (ref "CFG") (pin "3") (pinfunction "3_3") (pintype "passive"))
    )
    (net (code "100") (name "unconnected-(Q1-D-Pad4)") (class "Default")
      (node (ref "Q1") (pin "4") (pinfunction "D_4") (pintype "passive"))
    )
    (net (code "101") (name "unconnected-(Q2-D-Pad4)") (class "Default")
      (node (ref "Q2") (pin "4") (pinfunction "D_4") (pintype "passive"))
    )
    (net (code "102") (name "unconnected-(Q3-D-Pad4)") (class "Default")
      (node (ref "Q3") (pin "4") (pinfunction "D_4") (pintype "passive"))
    )
    (net (code "103") (name "unconnected-(Q4-D-Pad4)") (class "Default")
      (node (ref "Q4") (pin "4") (pinfunction "D_4") (pintype "passive"))
    )
    (net (code "104") (name "unconnected-(Q5-D-Pad4)") (class "Default")
      (node (ref "Q5") (pin "4") (pinfunction "D_4") (pintype "passive"))
    )
    (net (code "105") (name "unconnected-(Q6-D-Pad4)") (class "Default")
      (node (ref "Q6") (pin "4") (pinfunction "D_4") (pintype "passive"))
    )
    (net (code "106") (name "unconnected-(Q8-D-Pad4)") (class "Default")
      (node (ref "Q8") (pin "4") (pinfunction "D_4") (pintype "passive"))
    )
    (net (code "107") (name "unconnected-(Q9-D-Pad4)") (class "Default")
      (node (ref "Q9") (pin "4") (pinfunction "D_4") (pintype "passive"))
    )
    (net (code "108") (name "unconnected-(Q10-D-Pad4)") (class "Default")
      (node (ref "Q10") (pin "4") (pinfunction "D_4") (pintype "passive"))
    )
    (net (code "109") (name "unconnected-(RESET1-Pad1)") (class "Default")
      (node (ref "RESET1") (pin "1") (pinfunction "1_1") (pintype "passive"))
    )
    (net (code "110") (name "unconnected-(RESET1-Pad3)") (class "Default")
      (node (ref "RESET1") (pin "3") (pinfunction "3_3") (pintype "passive"))
    )
    (net (code "111") (name "unconnected-(U$2-EN1-Pad7)") (class "Default")
      (node (ref "U$2") (pin "7") (pinfunction "EN1_7") (pintype "input"))
    )
    (net (code "112") (name "unconnected-(U$2-EN2-Pad11)") (class "Default")
      (node (ref "U$2") (pin "11") (pinfunction "EN2_11") (pintype "input"))
    )
    (net (code "113") (name "unconnected-(U$2-EN3-Pad14)") (class "Default")
      (node (ref "U$2") (pin "14") (pinfunction "EN3_14") (pintype "input"))
    )
    (net (code "114") (name "unconnected-(U$2-EN4-Pad17)") (class "Default")
      (node (ref "U$2") (pin "17") (pinfunction "EN4_17") (pintype "input"))
    )
    (net (code "115") (name "unconnected-(U$2-EXPSCL1-Pad1)") (class "Default")
      (node (ref "U$2") (pin "1") (pinfunction "EXPSCL1_1") (pintype "bidirectional"))
    )
    (net (code "116") (name "unconnected-(U$2-EXPSCL2-Pad2)") (class "Default")
      (node (ref "U$2") (pin "2") (pinfunction "EXPSCL2_2") (pintype "bidirectional"))
    )
    (net (code "117") (name "unconnected-(U$2-EXPSDA1-Pad18)") (class "Default")
      (node (ref "U$2") (pin "18") (pinfunction "EXPSDA1_18") (pintype "bidirectional"))
    )
    (net (code "118") (name "unconnected-(U$2-EXPSDA2-Pad19)") (class "Default")
      (node (ref "U$2") (pin "19") (pinfunction "EXPSDA2_19") (pintype "bidirectional"))
    )
    (net (code "119") (name "unconnected-(U$3-PadRST)") (class "Default")
      (node (ref "U$3") (pin "RST") (pinfunction "RST_RST") (pintype "bidirectional"))
    )
    (net (code "120") (name "unconnected-(U1-AIO0-Pad9)") (class "Default")
      (node (ref "U1") (pin "9") (pinfunction "AIO0_9") (pintype "bidirectional"))
    )
    (net (code "121") (name "unconnected-(U1-AIO1-Pad10)") (class "Default")
      (node (ref "U1") (pin "10") (pinfunction "AIO1_10") (pintype "bidirectional"))
    )
    (net (code "122") (name "unconnected-(U1-CLK-Pad19)") (class "Default")
      (node (ref "U1") (pin "19") (pinfunction "CLK_19") (pintype "bidirectional"))
    )
    (net (code "123") (name "unconnected-(U1-CSB-Pad16)") (class "Default")
      (node (ref "U1") (pin "16") (pinfunction "CSB_16") (pintype "bidirectional"))
    )
    (net (code "124") (name "unconnected-(U1-CTS-Pad3)") (class "Default")
      (node (ref "U1") (pin "3") (pinfunction "CTS_3") (pintype "bidirectional"))
    )
    (net (code "125") (name "unconnected-(U1-GND1-Pad21)") (class "Default")
      (node (ref "U1") (pin "21") (pinfunction "GND1_21") (pintype "bidirectional"))
    )
    (net (code "126") (name "unconnected-(U1-GND2-Pad22)") (class "Default")
      (node (ref "U1") (pin "22") (pinfunction "GND2_22") (pintype "bidirectional"))
    )
    (net (code "127") (name "unconnected-(U1-MISO-Pad18)") (class "Default")
      (node (ref "U1") (pin "18") (pinfunction "MISO_18") (pintype "bidirectional"))
    )
    (net (code "128") (name "unconnected-(U1-MOSI-Pad17)") (class "Default")
      (node (ref "U1") (pin "17") (pinfunction "MOSI_17") (pintype "bidirectional"))
    )
    (net (code "129") (name "unconnected-(U1-NC-Pad14)") (class "Default")
      (node (ref "U1") (pin "14") (pinfunction "NC_14") (pintype "bidirectional"))
    )
    (net (code "130") (name "unconnected-(U1-PCM_CLK-Pad5)") (class "Default")
      (node (ref "U1") (pin "5") (pinfunction "PCM_CLK_5") (pintype "bidirectional"))
    )
    (net (code "131") (name "unconnected-(U1-PCM_IN-Pad7)") (class "Default")
      (node (ref "U1") (pin "7") (pinfunction "PCM_IN_7") (pintype "bidirectional"))
    )
    (net (code "132") (name "unconnected-(U1-PCM_OUT-Pad6)") (class "Default")
      (node (ref "U1") (pin "6") (pinfunction "PCM_OUT_6") (pintype "bidirectional"))
    )
    (net (code "133") (name "unconnected-(U1-PCN_SYNC-Pad8)") (class "Default")
      (node (ref "U1") (pin "8") (pinfunction "PCN_SYNC_8") (pintype "bidirectional"))
    )
    (net (code "134") (name "unconnected-(U1-PIO0-Pad23)") (class "Default")
      (node (ref "U1") (pin "23") (pinfunction "PIO0_23") (pintype "bidirectional"))
    )
    (net (code "135") (name "unconnected-(U1-PIO1-Pad24)") (class "Default")
      (node (ref "U1") (pin "24") (pinfunction "PIO1_24") (pintype "bidirectional"))
    )
    (net (code "136") (name "unconnected-(U1-PIO2-Pad25)") (class "Default")
      (node (ref "U1") (pin "25") (pinfunction "PIO2_25") (pintype "bidirectional"))
    )
    (net (code "137") (name "unconnected-(U1-PIO3-Pad26)") (class "Default")
      (node (ref "U1") (pin "26") (pinfunction "PIO3_26") (pintype "bidirectional"))
    )
    (net (code "138") (name "unconnected-(U1-PIO4-Pad27)") (class "Default")
      (node (ref "U1") (pin "27") (pinfunction "PIO4_27") (pintype "bidirectional"))
    )
    (net (code "139") (name "unconnected-(U1-PIO5-Pad28)") (class "Default")
      (node (ref "U1") (pin "28") (pinfunction "PIO5_28") (pintype "bidirectional"))
    )
    (net (code "140") (name "unconnected-(U1-PIO6-Pad29)") (class "Default")
      (node (ref "U1") (pin "29") (pinfunction "PIO6_29") (pintype "bidirectional"))
    )
    (net (code "141") (name "unconnected-(U1-PIO7-Pad30)") (class "Default")
      (node (ref "U1") (pin "30") (pinfunction "PIO7_30") (pintype "bidirectional"))
    )
    (net (code "142") (name "unconnected-(U1-PIO8-Pad31)") (class "Default")
      (node (ref "U1") (pin "31") (pinfunction "PIO8_31") (pintype "bidirectional"))
    )
    (net (code "143") (name "unconnected-(U1-PIO9-Pad32)") (class "Default")
      (node (ref "U1") (pin "32") (pinfunction "PIO9_32") (pintype "bidirectional"))
    )
    (net (code "144") (name "unconnected-(U1-PIO10-Pad33)") (class "Default")
      (node (ref "U1") (pin "33") (pinfunction "PIO10_33") (pintype "bidirectional"))
    )
    (net (code "145") (name "unconnected-(U1-PIO11-Pad34)") (class "Default")
      (node (ref "U1") (pin "34") (pinfunction "PIO11_34") (pintype "bidirectional"))
    )
    (net (code "146") (name "unconnected-(U1-RST-Pad11)") (class "Default")
      (node (ref "U1") (pin "11") (pinfunction "RST_11") (pintype "bidirectional"))
    )
    (net (code "147") (name "unconnected-(U1-RTS-Pad4)") (class "Default")
      (node (ref "U1") (pin "4") (pinfunction "RTS_4") (pintype "bidirectional"))
    )
    (net (code "148") (name "unconnected-(U1-VBUSD+-Pad20)") (class "Default")
      (node (ref "U1") (pin "20") (pinfunction "VBUSD+_20") (pintype "bidirectional"))
    )
    (net (code "149") (name "unconnected-(U1-VBUSD--Pad15)") (class "Default")
      (node (ref "U1") (pin "15") (pinfunction "VBUSD-_15") (pintype "bidirectional"))
    )
    (net (code "150") (name "unconnected-(X4-Pad4)") (class "Default")
      (node (ref "X4") (pin "4") (pinfunction "4_4") (pintype "passive"))
    )
  )
)
